# Digital_Isolation.net
KiCad netlist of a schematic drawn in Altium Designer
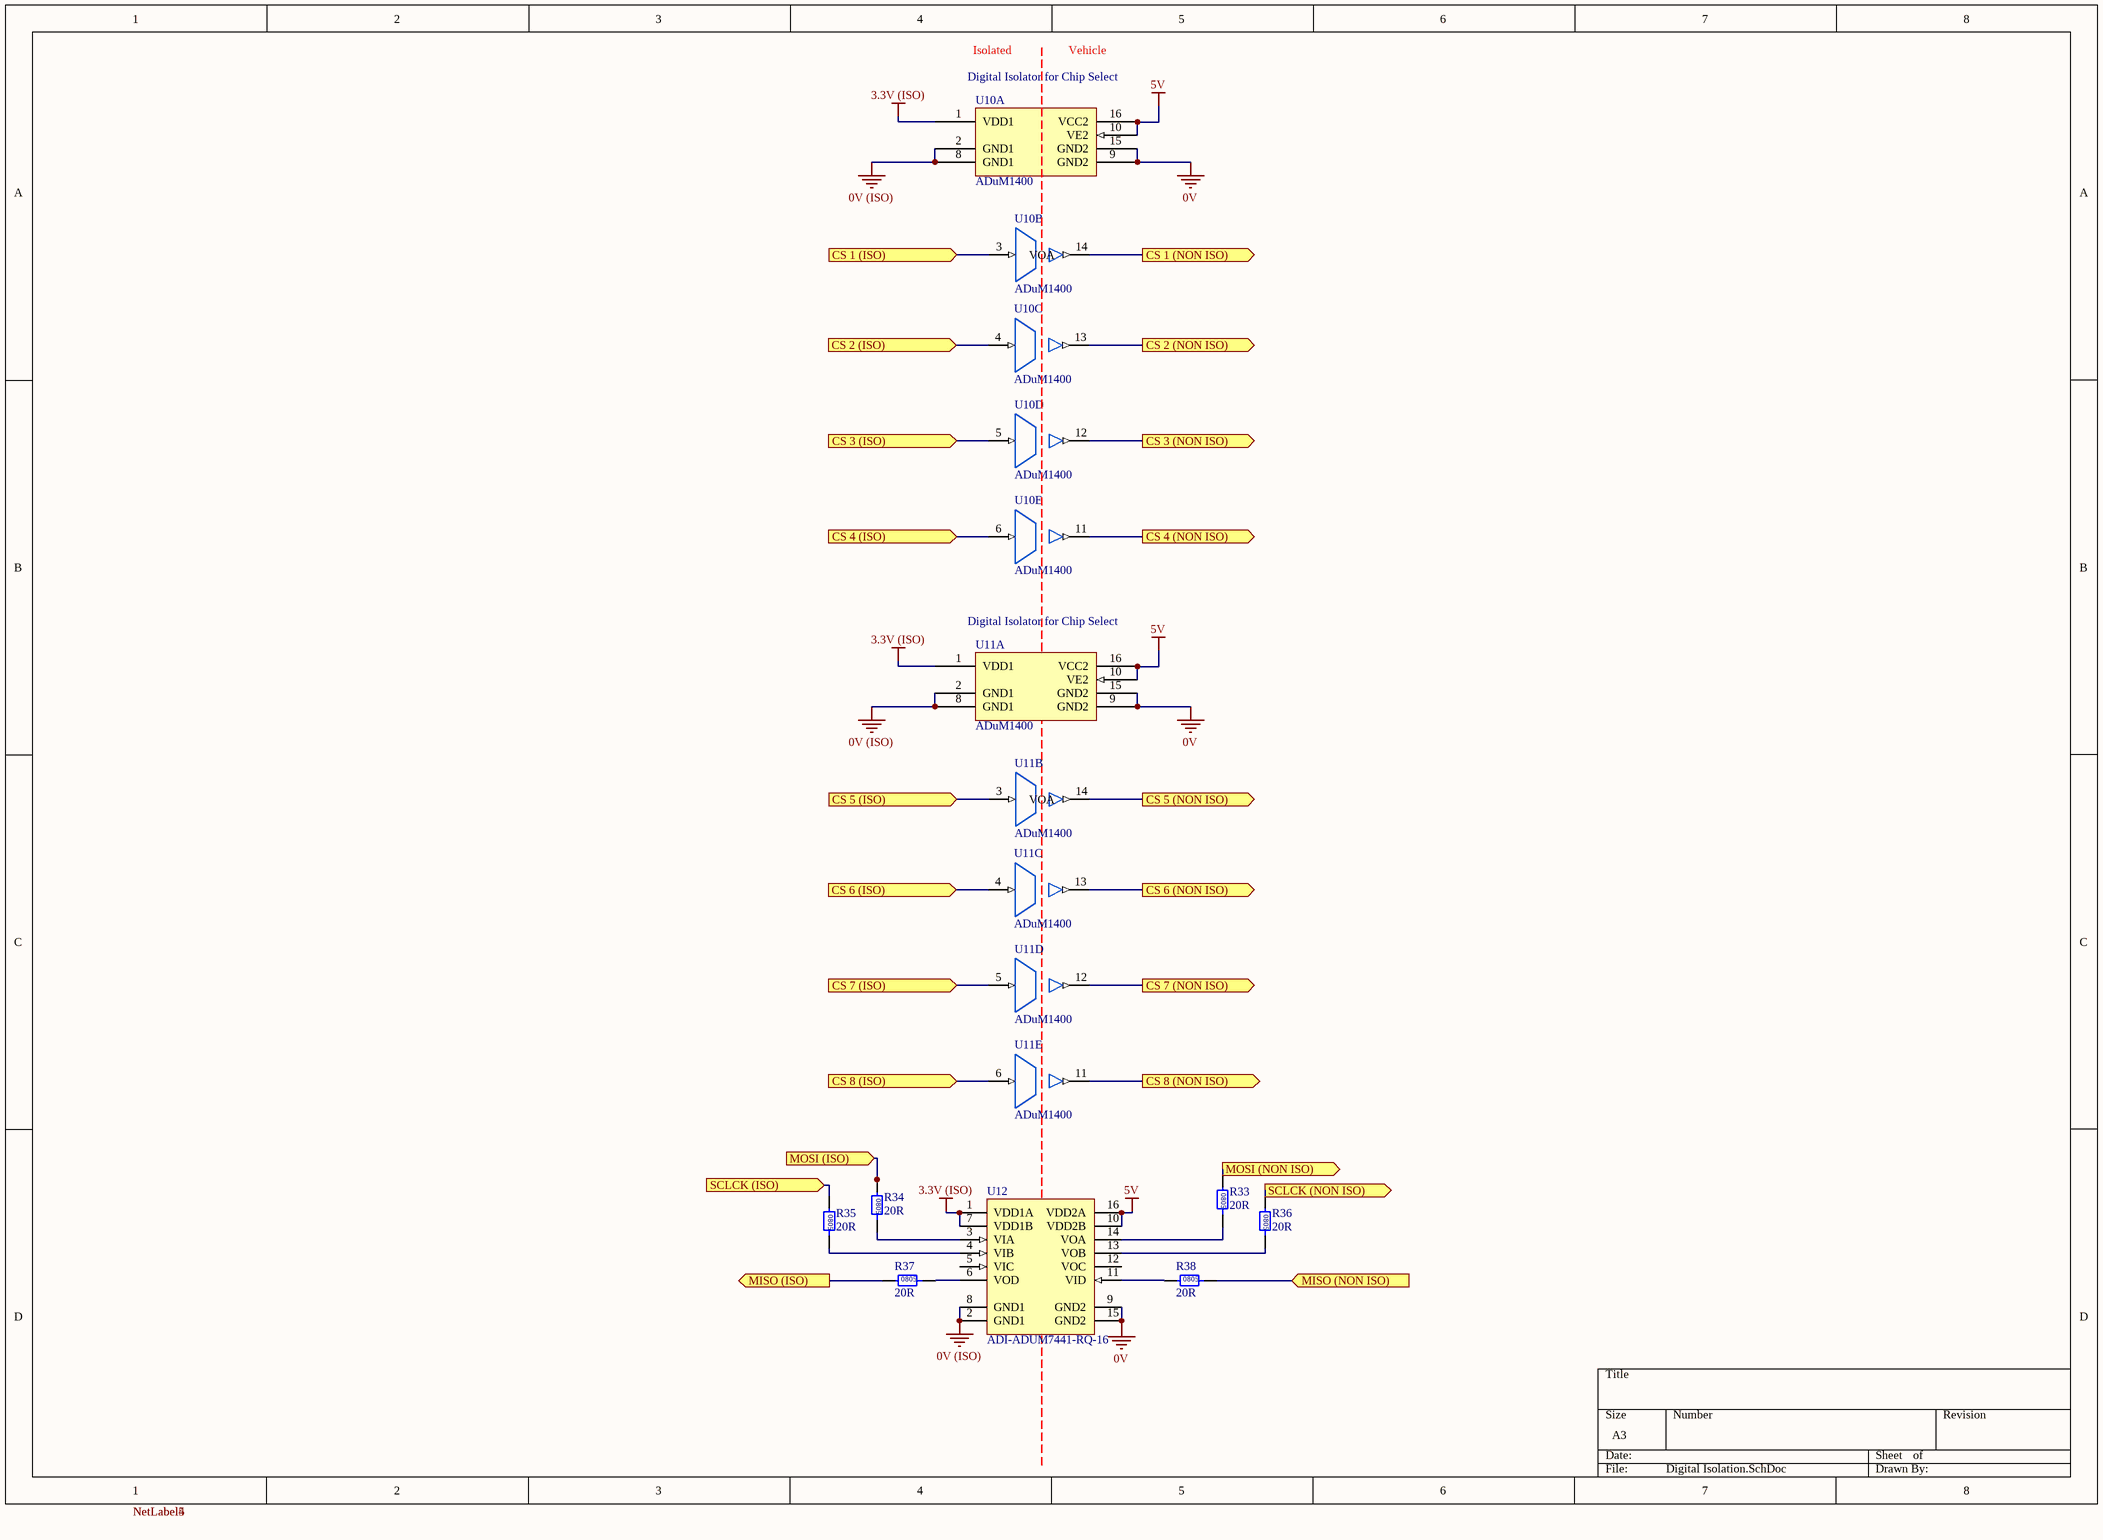
[diagram p0: Digital Isolation.SchDoc]

(export (version "E")
  (design (tool "Eeschema 10.0.6"))
  (components
    (comp (ref "R33")
      (value "20R")
      (footprint "0805")
      (fields
        (field (name "PART NUMBER") "RC0805FR0720RL")
        (field (name "MANUFACTURER") "YAGEO")
        (field (name "TOLERANCE") "0.01")
      )
      (libsource (lib "ts_standard_library") (part "Resistor 0805"))
    )
    (comp (ref "R34")
      (value "20R")
      (footprint "0805")
      (fields
        (field (name "PART NUMBER") "RC0805FR0720RL")
        (field (name "MANUFACTURER") "YAGEO")
        (field (name "TOLERANCE") "0.01")
      )
      (libsource (lib "ts_standard_library") (part "Resistor 0805"))
    )
    (comp (ref "R35")
      (value "20R")
      (footprint "0805")
      (fields
        (field (name "PART NUMBER") "RC0805FR0720RL")
        (field (name "MANUFACTURER") "YAGEO")
        (field (name "TOLERANCE") "0.01")
      )
      (libsource (lib "ts_standard_library") (part "Resistor 0805"))
    )
    (comp (ref "R36")
      (value "20R")
      (footprint "0805")
      (fields
        (field (name "PART NUMBER") "RC0805FR0720RL")
        (field (name "MANUFACTURER") "YAGEO")
        (field (name "TOLERANCE") "0.01")
      )
      (libsource (lib "ts_standard_library") (part "Resistor 0805"))
    )
    (comp (ref "R37")
      (value "20R")
      (footprint "0805")
      (fields
        (field (name "PART NUMBER") "RC0805FR0720RL")
        (field (name "MANUFACTURER") "YAGEO")
        (field (name "TOLERANCE") "0.01")
      )
      (libsource (lib "ts_standard_library") (part "Resistor 0805"))
    )
    (comp (ref "R38")
      (value "20R")
      (footprint "0805")
      (fields
        (field (name "PART NUMBER") "RC0805FR0720RL")
        (field (name "MANUFACTURER") "YAGEO")
        (field (name "TOLERANCE") "0.01")
      )
      (libsource (lib "ts_standard_library") (part "Resistor 0805"))
    )
    (comp (ref "U10")
      (value "ADuM1400")
      (footprint "AD 16-SOIC")
      (fields
        (field (name "MANUFACTURER") "Analog Devices")
        (field (name "DIGIKEY PART NUMBER") "ADUM1400WSRWZ-ND")
      )
      (libsource (lib "ts_standard_library") (part "ADuM1400"))
    )
    (comp (ref "U11")
      (value "ADuM1400")
      (footprint "AD 16-SOIC")
      (fields
        (field (name "MANUFACTURER") "Analog Devices")
        (field (name "DIGIKEY PART NUMBER") "ADUM1400WSRWZ-ND")
      )
      (libsource (lib "ts_standard_library") (part "ADuM1400"))
    )
    (comp (ref "U12")
      (value "ADI-ADUM7441-RQ-16")
      (footprint "ADI-RQ-16_M")
      (description "DGTL ISO 1000VRMS 4CH GP 16QSOP")
      (fields (field (name "PART NUMBER") "ADUM7441ARQZ-RL7") (field (name "MANUFACTURER") "Analog Devices"))
      (libsource (lib "ts_standard_library") (part "ADI-ADUM7441-RQ-16"))
    )
  )
  (nets
    (net (code "1") (name "/CS 1 (ISO)") (class "Default")
      (node (ref "U10") (pin "3") (pinfunction "VIA_3") (pintype "input"))
    )
    (net (code "2") (name "/CS 1 (NON ISO)") (class "Default")
      (node (ref "U10") (pin "14") (pinfunction "VOA_14") (pintype "output"))
    )
    (net (code "3") (name "/CS 2 (ISO)") (class "Default")
      (node (ref "U10") (pin "4") (pinfunction "VIB_4") (pintype "input"))
    )
    (net (code "4") (name "/CS 2 (NON ISO)") (class "Default")
      (node (ref "U10") (pin "13") (pinfunction "VOB_13") (pintype "output"))
    )
    (net (code "5") (name "/CS 3 (ISO)") (class "Default")
      (node (ref "U10") (pin "5") (pinfunction "VIC_5") (pintype "input"))
    )
    (net (code "6") (name "/CS 3 (NON ISO)") (class "Default")
      (node (ref "U10") (pin "12") (pinfunction "VOC_12") (pintype "output"))
    )
    (net (code "7") (name "/CS 4 (ISO)") (class "Default")
      (node (ref "U10") (pin "6") (pinfunction "VID_6") (pintype "input"))
    )
    (net (code "8") (name "/CS 4 (NON ISO)") (class "Default")
      (node (ref "U10") (pin "11") (pinfunction "VOD_11") (pintype "output"))
    )
    (net (code "9") (name "/CS 5 (ISO)") (class "Default")
      (node (ref "U11") (pin "3") (pinfunction "VIA_3") (pintype "input"))
    )
    (net (code "10") (name "/CS 5 (NON ISO)") (class "Default")
      (node (ref "U11") (pin "14") (pinfunction "VOA_14") (pintype "output"))
    )
    (net (code "11") (name "/CS 6 (ISO)") (class "Default")
      (node (ref "U11") (pin "4") (pinfunction "VIB_4") (pintype "input"))
    )
    (net (code "12") (name "/CS 6 (NON ISO)") (class "Default")
      (node (ref "U11") (pin "13") (pinfunction "VOB_13") (pintype "output"))
    )
    (net (code "13") (name "/CS 7 (ISO)") (class "Default")
      (node (ref "U11") (pin "5") (pinfunction "VIC_5") (pintype "input"))
    )
    (net (code "14") (name "/CS 7 (NON ISO)") (class "Default")
      (node (ref "U11") (pin "12") (pinfunction "VOC_12") (pintype "output"))
    )
    (net (code "15") (name "/CS 8 (ISO)") (class "Default")
      (node (ref "U11") (pin "6") (pinfunction "VID_6") (pintype "input"))
    )
    (net (code "16") (name "/CS 8 (NON ISO)") (class "Default")
      (node (ref "U11") (pin "11") (pinfunction "VOD_11") (pintype "output"))
    )
    (net (code "17") (name "/MISO (ISO)") (class "Default")
      (node (ref "R37") (pin "1") (pinfunction "1_1") (pintype "passive"))
    )
    (net (code "18") (name "/MISO (NON ISO)") (class "Default")
      (node (ref "R38") (pin "2") (pinfunction "2_2") (pintype "passive"))
    )
    (net (code "19") (name "/MOSI (ISO)") (class "Default")
      (node (ref "R34") (pin "1") (pinfunction "1_1") (pintype "passive"))
    )
    (net (code "20") (name "/MOSI (NON ISO)") (class "Default")
      (node (ref "R33") (pin "1") (pinfunction "1_1") (pintype "passive"))
    )
    (net (code "22") (name "/SCLCK (ISO)") (class "Default")
      (node (ref "R35") (pin "1") (pinfunction "1_1") (pintype "passive"))
    )
    (net (code "23") (name "/SCLCK (NON ISO)") (class "Default")
      (node (ref "R36") (pin "1") (pinfunction "1_1") (pintype "passive"))
    )
    (net (code "24") (name "0V") (class "Default")
      (node (ref "U10") (pin "15") (pinfunction "GND2_15") (pintype "power_in"))
      (node (ref "U10") (pin "9") (pinfunction "GND2_9") (pintype "power_in"))
      (node (ref "U11") (pin "15") (pinfunction "GND2_15") (pintype "power_in"))
      (node (ref "U11") (pin "9") (pinfunction "GND2_9") (pintype "power_in"))
      (node (ref "U12") (pin "15") (pinfunction "GND2_15") (pintype "power_in"))
      (node (ref "U12") (pin "9") (pinfunction "GND2_9") (pintype "power_in"))
    )
    (net (code "25") (name "0V (ISO)") (class "Default")
      (node (ref "U10") (pin "2") (pinfunction "GND1_2") (pintype "power_in"))
      (node (ref "U10") (pin "8") (pinfunction "GND1_8") (pintype "power_in"))
      (node (ref "U11") (pin "2") (pinfunction "GND1_2") (pintype "power_in"))
      (node (ref "U11") (pin "8") (pinfunction "GND1_8") (pintype "power_in"))
      (node (ref "U12") (pin "2") (pinfunction "GND1_2") (pintype "power_in"))
      (node (ref "U12") (pin "8") (pinfunction "GND1_8") (pintype "power_in"))
    )
    (net (code "26") (name "3.3V (ISO)") (class "Default")
      (node (ref "U10") (pin "1") (pinfunction "VDD1_1") (pintype "power_in"))
      (node (ref "U11") (pin "1") (pinfunction "VDD1_1") (pintype "power_in"))
      (node (ref "U12") (pin "1") (pinfunction "VDD1A_1") (pintype "power_in"))
      (node (ref "U12") (pin "7") (pinfunction "VDD1B_7") (pintype "power_in"))
    )
    (net (code "27") (name "5V") (class "Default")
      (node (ref "U10") (pin "10") (pinfunction "VE2_10") (pintype "input"))
      (node (ref "U10") (pin "16") (pinfunction "VCC2_16") (pintype "power_in"))
      (node (ref "U11") (pin "10") (pinfunction "VE2_10") (pintype "input"))
      (node (ref "U11") (pin "16") (pinfunction "VCC2_16") (pintype "power_in"))
      (node (ref "U12") (pin "10") (pinfunction "VDD2B_10") (pintype "power_in"))
      (node (ref "U12") (pin "16") (pinfunction "VDD2A_16") (pintype "power_in"))
    )
    (net (code "28") (name "Net-(U12-VIA)") (class "Default")
      (node (ref "R34") (pin "2") (pinfunction "2_2") (pintype "passive"))
      (node (ref "U12") (pin "3") (pinfunction "VIA_3") (pintype "input"))
    )
    (net (code "29") (name "Net-(U12-VIB)") (class "Default")
      (node (ref "R35") (pin "2") (pinfunction "2_2") (pintype "passive"))
      (node (ref "U12") (pin "4") (pinfunction "VIB_4") (pintype "input"))
    )
    (net (code "30") (name "Net-(U12-VID)") (class "Default")
      (node (ref "R38") (pin "1") (pinfunction "1_1") (pintype "passive"))
      (node (ref "U12") (pin "11") (pinfunction "VID_11") (pintype "input"))
    )
    (net (code "31") (name "Net-(U12-VOA)") (class "Default")
      (node (ref "R33") (pin "2") (pinfunction "2_2") (pintype "passive"))
      (node (ref "U12") (pin "14") (pinfunction "VOA_14") (pintype "tri_state"))
    )
    (net (code "32") (name "Net-(U12-VOB)") (class "Default")
      (node (ref "R36") (pin "2") (pinfunction "2_2") (pintype "passive"))
      (node (ref "U12") (pin "13") (pinfunction "VOB_13") (pintype "tri_state"))
    )
    (net (code "33") (name "Net-(U12-VOD)") (class "Default")
      (node (ref "R37") (pin "2") (pinfunction "2_2") (pintype "passive"))
      (node (ref "U12") (pin "6") (pinfunction "VOD_6") (pintype "tri_state"))
    )
    (net (code "34") (name "unconnected-(U12-VIC-Pad5)") (class "Default")
      (node (ref "U12") (pin "5") (pinfunction "VIC_5") (pintype "input"))
    )
    (net (code "35") (name "unconnected-(U12-VOC-Pad12)") (class "Default")
      (node (ref "U12") (pin "12") (pinfunction "VOC_12") (pintype "tri_state"))
    )
  )
)
